# exp30ac.net
KiCad netlist of a schematic drawn in EAGLE
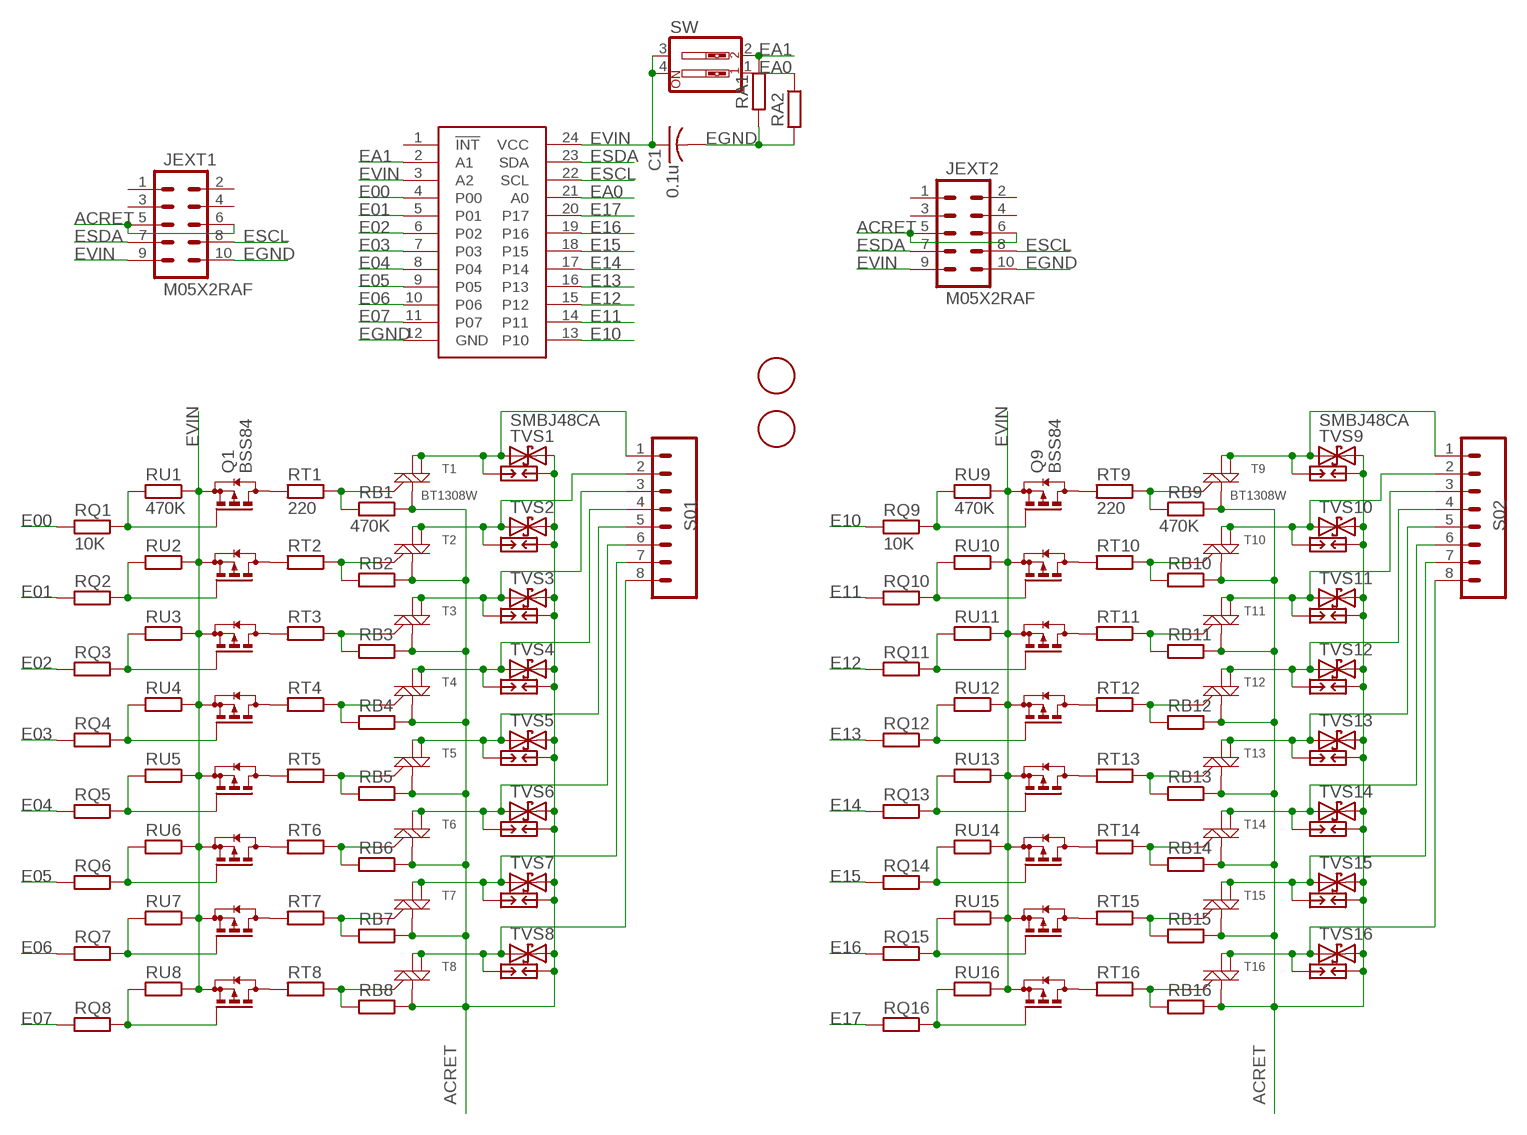
[diagram p0: schematic, sheet 1]

(export (version "E")
  (design (tool "Eeschema 10.0.6"))
  (components
    (comp (ref "C1")
      (value "0.1u")
      (footprint "eagle-import:C0603")
      (libsource (lib "eagle-import") (part "C-USC0603"))
    )
    (comp (ref "JEXT1")
      (value "M05X2RAF")
      (footprint "eagle-import:2X5-RAF")
      (libsource (lib "eagle-import") (part "M05X2RAF"))
    )
    (comp (ref "JEXT2")
      (value "M05X2RAF")
      (footprint "eagle-import:2X5-RAF")
      (libsource (lib "eagle-import") (part "M05X2RAF"))
    )
    (comp (ref "PCF8575")
      (value "PCF8575")
      (footprint "eagle-import:SSOP24")
      (libsource (lib "eagle-import") (part "PCF8575"))
    )
    (comp (ref "Q1")
      (value "BSS84")
      (footprint "eagle-import:SOT23")
      (libsource (lib "eagle-import") (part "BSS84"))
    )
    (comp (ref "Q2")
      (value "BSS84")
      (footprint "eagle-import:SOT23")
      (libsource (lib "eagle-import") (part "BSS84"))
    )
    (comp (ref "Q3")
      (value "BSS84")
      (footprint "eagle-import:SOT23")
      (libsource (lib "eagle-import") (part "BSS84"))
    )
    (comp (ref "Q4")
      (value "BSS84")
      (footprint "eagle-import:SOT23")
      (libsource (lib "eagle-import") (part "BSS84"))
    )
    (comp (ref "Q5")
      (value "BSS84")
      (footprint "eagle-import:SOT23")
      (libsource (lib "eagle-import") (part "BSS84"))
    )
    (comp (ref "Q6")
      (value "BSS84")
      (footprint "eagle-import:SOT23")
      (libsource (lib "eagle-import") (part "BSS84"))
    )
    (comp (ref "Q7")
      (value "BSS84")
      (footprint "eagle-import:SOT23")
      (libsource (lib "eagle-import") (part "BSS84"))
    )
    (comp (ref "Q8")
      (value "BSS84")
      (footprint "eagle-import:SOT23")
      (libsource (lib "eagle-import") (part "BSS84"))
    )
    (comp (ref "Q9")
      (value "BSS84")
      (footprint "eagle-import:SOT23")
      (libsource (lib "eagle-import") (part "BSS84"))
    )
    (comp (ref "Q10")
      (value "BSS84")
      (footprint "eagle-import:SOT23")
      (libsource (lib "eagle-import") (part "BSS84"))
    )
    (comp (ref "Q11")
      (value "BSS84")
      (footprint "eagle-import:SOT23")
      (libsource (lib "eagle-import") (part "BSS84"))
    )
    (comp (ref "Q12")
      (value "BSS84")
      (footprint "eagle-import:SOT23")
      (libsource (lib "eagle-import") (part "BSS84"))
    )
    (comp (ref "Q13")
      (value "BSS84")
      (footprint "eagle-import:SOT23")
      (libsource (lib "eagle-import") (part "BSS84"))
    )
    (comp (ref "Q14")
      (value "BSS84")
      (footprint "eagle-import:SOT23")
      (libsource (lib "eagle-import") (part "BSS84"))
    )
    (comp (ref "Q15")
      (value "BSS84")
      (footprint "eagle-import:SOT23")
      (libsource (lib "eagle-import") (part "BSS84"))
    )
    (comp (ref "Q16")
      (value "BSS84")
      (footprint "eagle-import:SOT23")
      (libsource (lib "eagle-import") (part "BSS84"))
    )
    (comp (ref "RA1")
      (value "10K")
      (footprint "eagle-import:R0603")
      (libsource (lib "eagle-import") (part "R-EU_R0603"))
    )
    (comp (ref "RA2")
      (value "10K")
      (footprint "eagle-import:R0603")
      (libsource (lib "eagle-import") (part "R-EU_R0603"))
    )
    (comp (ref "RB1")
      (value "470K")
      (footprint "eagle-import:R0603")
      (libsource (lib "eagle-import") (part "R-EU_R0603"))
    )
    (comp (ref "RB2")
      (value "470K")
      (footprint "eagle-import:R0603")
      (libsource (lib "eagle-import") (part "R-EU_R0603"))
    )
    (comp (ref "RB3")
      (value "470K")
      (footprint "eagle-import:R0603")
      (libsource (lib "eagle-import") (part "R-EU_R0603"))
    )
    (comp (ref "RB4")
      (value "470K")
      (footprint "eagle-import:R0603")
      (libsource (lib "eagle-import") (part "R-EU_R0603"))
    )
    (comp (ref "RB5")
      (value "470K")
      (footprint "eagle-import:R0603")
      (libsource (lib "eagle-import") (part "R-EU_R0603"))
    )
    (comp (ref "RB6")
      (value "470K")
      (footprint "eagle-import:R0603")
      (libsource (lib "eagle-import") (part "R-EU_R0603"))
    )
    (comp (ref "RB7")
      (value "470K")
      (footprint "eagle-import:R0603")
      (libsource (lib "eagle-import") (part "R-EU_R0603"))
    )
    (comp (ref "RB8")
      (value "470K")
      (footprint "eagle-import:R0603")
      (libsource (lib "eagle-import") (part "R-EU_R0603"))
    )
    (comp (ref "RB9")
      (value "470K")
      (footprint "eagle-import:R0603")
      (libsource (lib "eagle-import") (part "R-EU_R0603"))
    )
    (comp (ref "RB10")
      (value "470K")
      (footprint "eagle-import:R0603")
      (libsource (lib "eagle-import") (part "R-EU_R0603"))
    )
    (comp (ref "RB11")
      (value "470K")
      (footprint "eagle-import:R0603")
      (libsource (lib "eagle-import") (part "R-EU_R0603"))
    )
    (comp (ref "RB12")
      (value "470K")
      (footprint "eagle-import:R0603")
      (libsource (lib "eagle-import") (part "R-EU_R0603"))
    )
    (comp (ref "RB13")
      (value "470K")
      (footprint "eagle-import:R0603")
      (libsource (lib "eagle-import") (part "R-EU_R0603"))
    )
    (comp (ref "RB14")
      (value "470K")
      (footprint "eagle-import:R0603")
      (libsource (lib "eagle-import") (part "R-EU_R0603"))
    )
    (comp (ref "RB15")
      (value "470K")
      (footprint "eagle-import:R0603")
      (libsource (lib "eagle-import") (part "R-EU_R0603"))
    )
    (comp (ref "RB16")
      (value "470K")
      (footprint "eagle-import:R0603")
      (libsource (lib "eagle-import") (part "R-EU_R0603"))
    )
    (comp (ref "RQ1")
      (value "10K")
      (footprint "eagle-import:R0603")
      (libsource (lib "eagle-import") (part "R-EU_R0603"))
    )
    (comp (ref "RQ2")
      (value "10K")
      (footprint "eagle-import:R0603")
      (libsource (lib "eagle-import") (part "R-EU_R0603"))
    )
    (comp (ref "RQ3")
      (value "10K")
      (footprint "eagle-import:R0603")
      (libsource (lib "eagle-import") (part "R-EU_R0603"))
    )
    (comp (ref "RQ4")
      (value "10K")
      (footprint "eagle-import:R0603")
      (libsource (lib "eagle-import") (part "R-EU_R0603"))
    )
    (comp (ref "RQ5")
      (value "10K")
      (footprint "eagle-import:R0603")
      (libsource (lib "eagle-import") (part "R-EU_R0603"))
    )
    (comp (ref "RQ6")
      (value "10K")
      (footprint "eagle-import:R0603")
      (libsource (lib "eagle-import") (part "R-EU_R0603"))
    )
    (comp (ref "RQ7")
      (value "10K")
      (footprint "eagle-import:R0603")
      (libsource (lib "eagle-import") (part "R-EU_R0603"))
    )
    (comp (ref "RQ8")
      (value "10K")
      (footprint "eagle-import:R0603")
      (libsource (lib "eagle-import") (part "R-EU_R0603"))
    )
    (comp (ref "RQ9")
      (value "10K")
      (footprint "eagle-import:R0603")
      (libsource (lib "eagle-import") (part "R-EU_R0603"))
    )
    (comp (ref "RQ10")
      (value "10K")
      (footprint "eagle-import:R0603")
      (libsource (lib "eagle-import") (part "R-EU_R0603"))
    )
    (comp (ref "RQ11")
      (value "10K")
      (footprint "eagle-import:R0603")
      (libsource (lib "eagle-import") (part "R-EU_R0603"))
    )
    (comp (ref "RQ12")
      (value "10K")
      (footprint "eagle-import:R0603")
      (libsource (lib "eagle-import") (part "R-EU_R0603"))
    )
    (comp (ref "RQ13")
      (value "10K")
      (footprint "eagle-import:R0603")
      (libsource (lib "eagle-import") (part "R-EU_R0603"))
    )
    (comp (ref "RQ14")
      (value "10K")
      (footprint "eagle-import:R0603")
      (libsource (lib "eagle-import") (part "R-EU_R0603"))
    )
    (comp (ref "RQ15")
      (value "10K")
      (footprint "eagle-import:R0603")
      (libsource (lib "eagle-import") (part "R-EU_R0603"))
    )
    (comp (ref "RQ16")
      (value "10K")
      (footprint "eagle-import:R0603")
      (libsource (lib "eagle-import") (part "R-EU_R0603"))
    )
    (comp (ref "RT1")
      (value "220")
      (footprint "eagle-import:R0603")
      (libsource (lib "eagle-import") (part "R-EU_R0603"))
    )
    (comp (ref "RT2")
      (value "220")
      (footprint "eagle-import:R0603")
      (libsource (lib "eagle-import") (part "R-EU_R0603"))
    )
    (comp (ref "RT3")
      (value "220")
      (footprint "eagle-import:R0603")
      (libsource (lib "eagle-import") (part "R-EU_R0603"))
    )
    (comp (ref "RT4")
      (value "220")
      (footprint "eagle-import:R0603")
      (libsource (lib "eagle-import") (part "R-EU_R0603"))
    )
    (comp (ref "RT5")
      (value "220")
      (footprint "eagle-import:R0603")
      (libsource (lib "eagle-import") (part "R-EU_R0603"))
    )
    (comp (ref "RT6")
      (value "220")
      (footprint "eagle-import:R0603")
      (libsource (lib "eagle-import") (part "R-EU_R0603"))
    )
    (comp (ref "RT7")
      (value "220")
      (footprint "eagle-import:R0603")
      (libsource (lib "eagle-import") (part "R-EU_R0603"))
    )
    (comp (ref "RT8")
      (value "220")
      (footprint "eagle-import:R0603")
      (libsource (lib "eagle-import") (part "R-EU_R0603"))
    )
    (comp (ref "RT9")
      (value "220")
      (footprint "eagle-import:R0603")
      (libsource (lib "eagle-import") (part "R-EU_R0603"))
    )
    (comp (ref "RT10")
      (value "220")
      (footprint "eagle-import:R0603")
      (libsource (lib "eagle-import") (part "R-EU_R0603"))
    )
    (comp (ref "RT11")
      (value "220")
      (footprint "eagle-import:R0603")
      (libsource (lib "eagle-import") (part "R-EU_R0603"))
    )
    (comp (ref "RT12")
      (value "220")
      (footprint "eagle-import:R0603")
      (libsource (lib "eagle-import") (part "R-EU_R0603"))
    )
    (comp (ref "RT13")
      (value "220")
      (footprint "eagle-import:R0603")
      (libsource (lib "eagle-import") (part "R-EU_R0603"))
    )
    (comp (ref "RT14")
      (value "220")
      (footprint "eagle-import:R0603")
      (libsource (lib "eagle-import") (part "R-EU_R0603"))
    )
    (comp (ref "RT15")
      (value "220")
      (footprint "eagle-import:R0603")
      (libsource (lib "eagle-import") (part "R-EU_R0603"))
    )
    (comp (ref "RT16")
      (value "220")
      (footprint "eagle-import:R0603")
      (libsource (lib "eagle-import") (part "R-EU_R0603"))
    )
    (comp (ref "RU1")
      (value "470K")
      (footprint "eagle-import:R0603")
      (libsource (lib "eagle-import") (part "R-EU_R0603"))
    )
    (comp (ref "RU2")
      (value "470K")
      (footprint "eagle-import:R0603")
      (libsource (lib "eagle-import") (part "R-EU_R0603"))
    )
    (comp (ref "RU3")
      (value "470K")
      (footprint "eagle-import:R0603")
      (libsource (lib "eagle-import") (part "R-EU_R0603"))
    )
    (comp (ref "RU4")
      (value "470K")
      (footprint "eagle-import:R0603")
      (libsource (lib "eagle-import") (part "R-EU_R0603"))
    )
    (comp (ref "RU5")
      (value "470K")
      (footprint "eagle-import:R0603")
      (libsource (lib "eagle-import") (part "R-EU_R0603"))
    )
    (comp (ref "RU6")
      (value "470K")
      (footprint "eagle-import:R0603")
      (libsource (lib "eagle-import") (part "R-EU_R0603"))
    )
    (comp (ref "RU7")
      (value "470K")
      (footprint "eagle-import:R0603")
      (libsource (lib "eagle-import") (part "R-EU_R0603"))
    )
    (comp (ref "RU8")
      (value "470K")
      (footprint "eagle-import:R0603")
      (libsource (lib "eagle-import") (part "R-EU_R0603"))
    )
    (comp (ref "RU9")
      (value "470K")
      (footprint "eagle-import:R0603")
      (libsource (lib "eagle-import") (part "R-EU_R0603"))
    )
    (comp (ref "RU10")
      (value "470K")
      (footprint "eagle-import:R0603")
      (libsource (lib "eagle-import") (part "R-EU_R0603"))
    )
    (comp (ref "RU11")
      (value "470K")
      (footprint "eagle-import:R0603")
      (libsource (lib "eagle-import") (part "R-EU_R0603"))
    )
    (comp (ref "RU12")
      (value "470K")
      (footprint "eagle-import:R0603")
      (libsource (lib "eagle-import") (part "R-EU_R0603"))
    )
    (comp (ref "RU13")
      (value "470K")
      (footprint "eagle-import:R0603")
      (libsource (lib "eagle-import") (part "R-EU_R0603"))
    )
    (comp (ref "RU14")
      (value "470K")
      (footprint "eagle-import:R0603")
      (libsource (lib "eagle-import") (part "R-EU_R0603"))
    )
    (comp (ref "RU15")
      (value "470K")
      (footprint "eagle-import:R0603")
      (libsource (lib "eagle-import") (part "R-EU_R0603"))
    )
    (comp (ref "RU16")
      (value "470K")
      (footprint "eagle-import:R0603")
      (libsource (lib "eagle-import") (part "R-EU_R0603"))
    )
    (comp (ref "S01")
      (value "M085MM-8")
      (footprint "eagle-import:SCREWTERMINAL-5MM-8")
      (libsource (lib "eagle-import") (part "M085MM-8"))
    )
    (comp (ref "S02")
      (value "M085MM-8")
      (footprint "eagle-import:SCREWTERMINAL-5MM-8")
      (libsource (lib "eagle-import") (part "M085MM-8"))
    )
    (comp (ref "SP1")
      (value "PCB-SGAP")
      (footprint "eagle-import:PCB-SGAP")
      (libsource (lib "eagle-import") (part "PCB-SGAP"))
    )
    (comp (ref "SP2")
      (value "PCB-SGAP")
      (footprint "eagle-import:PCB-SGAP")
      (libsource (lib "eagle-import") (part "PCB-SGAP"))
    )
    (comp (ref "SP3")
      (value "PCB-SGAP")
      (footprint "eagle-import:PCB-SGAP")
      (libsource (lib "eagle-import") (part "PCB-SGAP"))
    )
    (comp (ref "SP4")
      (value "PCB-SGAP")
      (footprint "eagle-import:PCB-SGAP")
      (libsource (lib "eagle-import") (part "PCB-SGAP"))
    )
    (comp (ref "SP5")
      (value "PCB-SGAP")
      (footprint "eagle-import:PCB-SGAP")
      (libsource (lib "eagle-import") (part "PCB-SGAP"))
    )
    (comp (ref "SP6")
      (value "PCB-SGAP")
      (footprint "eagle-import:PCB-SGAP")
      (libsource (lib "eagle-import") (part "PCB-SGAP"))
    )
    (comp (ref "SP7")
      (value "PCB-SGAP")
      (footprint "eagle-import:PCB-SGAP")
      (libsource (lib "eagle-import") (part "PCB-SGAP"))
    )
    (comp (ref "SP8")
      (value "PCB-SGAP")
      (footprint "eagle-import:PCB-SGAP")
      (libsource (lib "eagle-import") (part "PCB-SGAP"))
    )
    (comp (ref "SP9")
      (value "PCB-SGAP")
      (footprint "eagle-import:PCB-SGAP")
      (libsource (lib "eagle-import") (part "PCB-SGAP"))
    )
    (comp (ref "SP10")
      (value "PCB-SGAP")
      (footprint "eagle-import:PCB-SGAP")
      (libsource (lib "eagle-import") (part "PCB-SGAP"))
    )
    (comp (ref "SP11")
      (value "PCB-SGAP")
      (footprint "eagle-import:PCB-SGAP")
      (libsource (lib "eagle-import") (part "PCB-SGAP"))
    )
    (comp (ref "SP12")
      (value "PCB-SGAP")
      (footprint "eagle-import:PCB-SGAP")
      (libsource (lib "eagle-import") (part "PCB-SGAP"))
    )
    (comp (ref "SP13")
      (value "PCB-SGAP")
      (footprint "eagle-import:PCB-SGAP")
      (libsource (lib "eagle-import") (part "PCB-SGAP"))
    )
    (comp (ref "SP14")
      (value "PCB-SGAP")
      (footprint "eagle-import:PCB-SGAP")
      (libsource (lib "eagle-import") (part "PCB-SGAP"))
    )
    (comp (ref "SP15")
      (value "PCB-SGAP")
      (footprint "eagle-import:PCB-SGAP")
      (libsource (lib "eagle-import") (part "PCB-SGAP"))
    )
    (comp (ref "SP16")
      (value "PCB-SGAP")
      (footprint "eagle-import:PCB-SGAP")
      (libsource (lib "eagle-import") (part "PCB-SGAP"))
    )
    (comp (ref "SW")
      (value "SW_DIP-2")
      (footprint "eagle-import:DIPSWITCH-02")
      (libsource (lib "eagle-import") (part "SW_DIP-2"))
    )
    (comp (ref "T1")
      (value "BT1308W")
      (footprint "eagle-import:SOT223")
      (libsource (lib "eagle-import") (part "MAC97SOT223"))
    )
    (comp (ref "T2")
      (value "MAC97SOT223")
      (footprint "eagle-import:SOT223")
      (libsource (lib "eagle-import") (part "MAC97SOT223"))
    )
    (comp (ref "T3")
      (value "MAC97SOT223")
      (footprint "eagle-import:SOT223")
      (libsource (lib "eagle-import") (part "MAC97SOT223"))
    )
    (comp (ref "T4")
      (value "MAC97SOT223")
      (footprint "eagle-import:SOT223")
      (libsource (lib "eagle-import") (part "MAC97SOT223"))
    )
    (comp (ref "T5")
      (value "MAC97SOT223")
      (footprint "eagle-import:SOT223")
      (libsource (lib "eagle-import") (part "MAC97SOT223"))
    )
    (comp (ref "T6")
      (value "MAC97SOT223")
      (footprint "eagle-import:SOT223")
      (libsource (lib "eagle-import") (part "MAC97SOT223"))
    )
    (comp (ref "T7")
      (value "MAC97SOT223")
      (footprint "eagle-import:SOT223")
      (libsource (lib "eagle-import") (part "MAC97SOT223"))
    )
    (comp (ref "T8")
      (value "MAC97SOT223")
      (footprint "eagle-import:SOT223")
      (libsource (lib "eagle-import") (part "MAC97SOT223"))
    )
    (comp (ref "T9")
      (value "BT1308W")
      (footprint "eagle-import:SOT223")
      (libsource (lib "eagle-import") (part "MAC97SOT223"))
    )
    (comp (ref "T10")
      (value "MAC97SOT223")
      (footprint "eagle-import:SOT223")
      (libsource (lib "eagle-import") (part "MAC97SOT223"))
    )
    (comp (ref "T11")
      (value "MAC97SOT223")
      (footprint "eagle-import:SOT223")
      (libsource (lib "eagle-import") (part "MAC97SOT223"))
    )
    (comp (ref "T12")
      (value "MAC97SOT223")
      (footprint "eagle-import:SOT223")
      (libsource (lib "eagle-import") (part "MAC97SOT223"))
    )
    (comp (ref "T13")
      (value "MAC97SOT223")
      (footprint "eagle-import:SOT223")
      (libsource (lib "eagle-import") (part "MAC97SOT223"))
    )
    (comp (ref "T14")
      (value "MAC97SOT223")
      (footprint "eagle-import:SOT223")
      (libsource (lib "eagle-import") (part "MAC97SOT223"))
    )
    (comp (ref "T15")
      (value "MAC97SOT223")
      (footprint "eagle-import:SOT223")
      (libsource (lib "eagle-import") (part "MAC97SOT223"))
    )
    (comp (ref "T16")
      (value "MAC97SOT223")
      (footprint "eagle-import:SOT223")
      (libsource (lib "eagle-import") (part "MAC97SOT223"))
    )
    (comp (ref "TVS1")
      (value "SMBJ48CA")
      (footprint "eagle-import:SMB")
      (libsource (lib "eagle-import") (part "TVSSMB"))
    )
    (comp (ref "TVS2")
      (value "TVSSMB")
      (footprint "eagle-import:SMB")
      (libsource (lib "eagle-import") (part "TVSSMB"))
    )
    (comp (ref "TVS3")
      (value "TVSSMB")
      (footprint "eagle-import:SMB")
      (libsource (lib "eagle-import") (part "TVSSMB"))
    )
    (comp (ref "TVS4")
      (value "TVSSMB")
      (footprint "eagle-import:SMB")
      (libsource (lib "eagle-import") (part "TVSSMB"))
    )
    (comp (ref "TVS5")
      (value "TVSSMB")
      (footprint "eagle-import:SMB")
      (libsource (lib "eagle-import") (part "TVSSMB"))
    )
    (comp (ref "TVS6")
      (value "TVSSMB")
      (footprint "eagle-import:SMB")
      (libsource (lib "eagle-import") (part "TVSSMB"))
    )
    (comp (ref "TVS7")
      (value "TVSSMB")
      (footprint "eagle-import:SMB")
      (libsource (lib "eagle-import") (part "TVSSMB"))
    )
    (comp (ref "TVS8")
      (value "TVSSMB")
      (footprint "eagle-import:SMB")
      (libsource (lib "eagle-import") (part "TVSSMB"))
    )
    (comp (ref "TVS9")
      (value "SMBJ48CA")
      (footprint "eagle-import:SMB")
      (libsource (lib "eagle-import") (part "TVSSMB"))
    )
    (comp (ref "TVS10")
      (value "TVSSMB")
      (footprint "eagle-import:SMB")
      (libsource (lib "eagle-import") (part "TVSSMB"))
    )
    (comp (ref "TVS11")
      (value "TVSSMB")
      (footprint "eagle-import:SMB")
      (libsource (lib "eagle-import") (part "TVSSMB"))
    )
    (comp (ref "TVS12")
      (value "TVSSMB")
      (footprint "eagle-import:SMB")
      (libsource (lib "eagle-import") (part "TVSSMB"))
    )
    (comp (ref "TVS13")
      (value "TVSSMB")
      (footprint "eagle-import:SMB")
      (libsource (lib "eagle-import") (part "TVSSMB"))
    )
    (comp (ref "TVS14")
      (value "TVSSMB")
      (footprint "eagle-import:SMB")
      (libsource (lib "eagle-import") (part "TVSSMB"))
    )
    (comp (ref "TVS15")
      (value "TVSSMB")
      (footprint "eagle-import:SMB")
      (libsource (lib "eagle-import") (part "TVSSMB"))
    )
    (comp (ref "TVS16")
      (value "TVSSMB")
      (footprint "eagle-import:SMB")
      (libsource (lib "eagle-import") (part "TVSSMB"))
    )
    (comp (ref "U$1")
      (value "FIDUCIAL")
      (footprint "eagle-import:FIDUCIAL_1MM")
      (libsource (lib "eagle-import") (part "FIDUCIAL"))
    )
    (comp (ref "U$2")
      (value "FIDUCIAL")
      (footprint "eagle-import:FIDUCIAL_1MM")
      (libsource (lib "eagle-import") (part "FIDUCIAL"))
    )
  )
  (nets
    (net (code "1") (name "/ACRET") (class "Default")
      (node (ref "JEXT1") (pin "5") (pinfunction "5_5") (pintype "passive"))
      (node (ref "JEXT1") (pin "6") (pinfunction "6_6") (pintype "passive"))
      (node (ref "JEXT2") (pin "5") (pinfunction "5_5") (pintype "passive"))
      (node (ref "JEXT2") (pin "6") (pinfunction "6_6") (pintype "passive"))
      (node (ref "RB1") (pin "1") (pinfunction "1_1") (pintype "passive"))
      (node (ref "RB10") (pin "1") (pinfunction "1_1") (pintype "passive"))
      (node (ref "RB11") (pin "1") (pinfunction "1_1") (pintype "passive"))
      (node (ref "RB12") (pin "1") (pinfunction "1_1") (pintype "passive"))
      (node (ref "RB13") (pin "1") (pinfunction "1_1") (pintype "passive"))
      (node (ref "RB14") (pin "1") (pinfunction "1_1") (pintype "passive"))
      (node (ref "RB15") (pin "1") (pinfunction "1_1") (pintype "passive"))
      (node (ref "RB16") (pin "1") (pinfunction "1_1") (pintype "passive"))
      (node (ref "RB2") (pin "1") (pinfunction "1_1") (pintype "passive"))
      (node (ref "RB3") (pin "1") (pinfunction "1_1") (pintype "passive"))
      (node (ref "RB4") (pin "1") (pinfunction "1_1") (pintype "passive"))
      (node (ref "RB5") (pin "1") (pinfunction "1_1") (pintype "passive"))
      (node (ref "RB6") (pin "1") (pinfunction "1_1") (pintype "passive"))
      (node (ref "RB7") (pin "1") (pinfunction "1_1") (pintype "passive"))
      (node (ref "RB8") (pin "1") (pinfunction "1_1") (pintype "passive"))
      (node (ref "RB9") (pin "1") (pinfunction "1_1") (pintype "passive"))
      (node (ref "SP1") (pin "1") (pinfunction "1_1") (pintype "passive"))
      (node (ref "SP10") (pin "1") (pinfunction "1_1") (pintype "passive"))
      (node (ref "SP11") (pin "1") (pinfunction "1_1") (pintype "passive"))
      (node (ref "SP12") (pin "1") (pinfunction "1_1") (pintype "passive"))
      (node (ref "SP13") (pin "1") (pinfunction "1_1") (pintype "passive"))
      (node (ref "SP14") (pin "1") (pinfunction "1_1") (pintype "passive"))
      (node (ref "SP15") (pin "1") (pinfunction "1_1") (pintype "passive"))
      (node (ref "SP16") (pin "1") (pinfunction "1_1") (pintype "passive"))
      (node (ref "SP2") (pin "1") (pinfunction "1_1") (pintype "passive"))
      (node (ref "SP3") (pin "1") (pinfunction "1_1") (pintype "passive"))
      (node (ref "SP4") (pin "1") (pinfunction "1_1") (pintype "passive"))
      (node (ref "SP5") (pin "1") (pinfunction "1_1") (pintype "passive"))
      (node (ref "SP6") (pin "1") (pinfunction "1_1") (pintype "passive"))
      (node (ref "SP7") (pin "1") (pinfunction "1_1") (pintype "passive"))
      (node (ref "SP8") (pin "1") (pinfunction "1_1") (pintype "passive"))
      (node (ref "SP9") (pin "1") (pinfunction "1_1") (pintype "passive"))
      (node (ref "T1") (pin "1") (pinfunction "M1_1") (pintype "bidirectional"))
      (node (ref "T10") (pin "1") (pinfunction "M1_1") (pintype "bidirectional"))
      (node (ref "T11") (pin "1") (pinfunction "M1_1") (pintype "bidirectional"))
      (node (ref "T12") (pin "1") (pinfunction "M1_1") (pintype "bidirectional"))
      (node (ref "T13") (pin "1") (pinfunction "M1_1") (pintype "bidirectional"))
      (node (ref "T14") (pin "1") (pinfunction "M1_1") (pintype "bidirectional"))
      (node (ref "T15") (pin "1") (pinfunction "M1_1") (pintype "bidirectional"))
      (node (ref "T16") (pin "1") (pinfunction "M1_1") (pintype "bidirectional"))
      (node (ref "T2") (pin "1") (pinfunction "M1_1") (pintype "bidirectional"))
      (node (ref "T3") (pin "1") (pinfunction "M1_1") (pintype "bidirectional"))
      (node (ref "T4") (pin "1") (pinfunction "M1_1") (pintype "bidirectional"))
      (node (ref "T5") (pin "1") (pinfunction "M1_1") (pintype "bidirectional"))
      (node (ref "T6") (pin "1") (pinfunction "M1_1") (pintype "bidirectional"))
      (node (ref "T7") (pin "1") (pinfunction "M1_1") (pintype "bidirectional"))
      (node (ref "T8") (pin "1") (pinfunction "M1_1") (pintype "bidirectional"))
      (node (ref "T9") (pin "1") (pinfunction "M1_1") (pintype "bidirectional"))
      (node (ref "TVS1") (pin "C") (pinfunction "C_C") (pintype "passive"))
      (node (ref "TVS10") (pin "C") (pinfunction "C_C") (pintype "passive"))
      (node (ref "TVS11") (pin "C") (pinfunction "C_C") (pintype "passive"))
      (node (ref "TVS12") (pin "C") (pinfunction "C_C") (pintype "passive"))
      (node (ref "TVS13") (pin "C") (pinfunction "C_C") (pintype "passive"))
      (node (ref "TVS14") (pin "C") (pinfunction "C_C") (pintype "passive"))
      (node (ref "TVS15") (pin "C") (pinfunction "C_C") (pintype "passive"))
      (node (ref "TVS16") (pin "C") (pinfunction "C_C") (pintype "passive"))
      (node (ref "TVS2") (pin "C") (pinfunction "C_C") (pintype "passive"))
      (node (ref "TVS3") (pin "C") (pinfunction "C_C") (pintype "passive"))
      (node (ref "TVS4") (pin "C") (pinfunction "C_C") (pintype "passive"))
      (node (ref "TVS5") (pin "C") (pinfunction "C_C") (pintype "passive"))
      (node (ref "TVS6") (pin "C") (pinfunction "C_C") (pintype "passive"))
      (node (ref "TVS7") (pin "C") (pinfunction "C_C") (pintype "passive"))
      (node (ref "TVS8") (pin "C") (pinfunction "C_C") (pintype "passive"))
      (node (ref "TVS9") (pin "C") (pinfunction "C_C") (pintype "passive"))
    )
    (net (code "2") (name "/E00") (class "Default")
      (node (ref "PCF8575") (pin "4") (pinfunction "P00_4") (pintype "bidirectional"))
      (node (ref "RQ1") (pin "2") (pinfunction "2_2") (pintype "passive"))
    )
    (net (code "3") (name "/E01") (class "Default")
      (node (ref "PCF8575") (pin "5") (pinfunction "P01_5") (pintype "bidirectional"))
      (node (ref "RQ2") (pin "2") (pinfunction "2_2") (pintype "passive"))
    )
    (net (code "4") (name "/E02") (class "Default")
      (node (ref "PCF8575") (pin "6") (pinfunction "P02_6") (pintype "bidirectional"))
      (node (ref "RQ3") (pin "2") (pinfunction "2_2") (pintype "passive"))
    )
    (net (code "5") (name "/E03") (class "Default")
      (node (ref "PCF8575") (pin "7") (pinfunction "P03_7") (pintype "bidirectional"))
      (node (ref "RQ4") (pin "2") (pinfunction "2_2") (pintype "passive"))
    )
    (net (code "6") (name "/E04") (class "Default")
      (node (ref "PCF8575") (pin "8") (pinfunction "P04_8") (pintype "bidirectional"))
      (node (ref "RQ5") (pin "2") (pinfunction "2_2") (pintype "passive"))
    )
    (net (code "7") (name "/E05") (class "Default")
      (node (ref "PCF8575") (pin "9") (pinfunction "P05_9") (pintype "bidirectional"))
      (node (ref "RQ6") (pin "2") (pinfunction "2_2") (pintype "passive"))
    )
    (net (code "8") (name "/E06") (class "Default")
      (node (ref "PCF8575") (pin "10") (pinfunction "P06_10") (pintype "bidirectional"))
      (node (ref "RQ7") (pin "2") (pinfunction "2_2") (pintype "passive"))
    )
    (net (code "9") (name "/E07") (class "Default")
      (node (ref "PCF8575") (pin "11") (pinfunction "P07_11") (pintype "bidirectional"))
      (node (ref "RQ8") (pin "2") (pinfunction "2_2") (pintype "passive"))
    )
    (net (code "10") (name "/E10") (class "Default")
      (node (ref "PCF8575") (pin "13") (pinfunction "P10_13") (pintype "bidirectional"))
      (node (ref "RQ9") (pin "2") (pinfunction "2_2") (pintype "passive"))
    )
    (net (code "11") (name "/E11") (class "Default")
      (node (ref "PCF8575") (pin "14") (pinfunction "P11_14") (pintype "bidirectional"))
      (node (ref "RQ10") (pin "2") (pinfunction "2_2") (pintype "passive"))
    )
    (net (code "12") (name "/E12") (class "Default")
      (node (ref "PCF8575") (pin "15") (pinfunction "P12_15") (pintype "bidirectional"))
      (node (ref "RQ11") (pin "2") (pinfunction "2_2") (pintype "passive"))
    )
    (net (code "13") (name "/E13") (class "Default")
      (node (ref "PCF8575") (pin "16") (pinfunction "P13_16") (pintype "bidirectional"))
      (node (ref "RQ12") (pin "2") (pinfunction "2_2") (pintype "passive"))
    )
    (net (code "14") (name "/E14") (class "Default")
      (node (ref "PCF8575") (pin "17") (pinfunction "P14_17") (pintype "bidirectional"))
      (node (ref "RQ13") (pin "2") (pinfunction "2_2") (pintype "passive"))
    )
    (net (code "15") (name "/E15") (class "Default")
      (node (ref "PCF8575") (pin "18") (pinfunction "P15_18") (pintype "bidirectional"))
      (node (ref "RQ14") (pin "2") (pinfunction "2_2") (pintype "passive"))
    )
    (net (code "16") (name "/E16") (class "Default")
      (node (ref "PCF8575") (pin "19") (pinfunction "P16_19") (pintype "bidirectional"))
      (node (ref "RQ15") (pin "2") (pinfunction "2_2") (pintype "passive"))
    )
    (net (code "17") (name "/E17") (class "Default")
      (node (ref "PCF8575") (pin "20") (pinfunction "P17_20") (pintype "bidirectional"))
      (node (ref "RQ16") (pin "2") (pinfunction "2_2") (pintype "passive"))
    )
    (net (code "18") (name "/EA0") (class "Default")
      (node (ref "PCF8575") (pin "21") (pinfunction "A0_21") (pintype "bidirectional"))
      (node (ref "RA2") (pin "1") (pinfunction "1_1") (pintype "passive"))
      (node (ref "SW") (pin "1") (pinfunction "1_1") (pintype "passive"))
    )
    (net (code "19") (name "/EA1") (class "Default")
      (node (ref "PCF8575") (pin "2") (pinfunction "A1_2") (pintype "bidirectional"))
      (node (ref "RA1") (pin "1") (pinfunction "1_1") (pintype "passive"))
      (node (ref "SW") (pin "2") (pinfunction "2_2") (pintype "passive"))
    )
    (net (code "20") (name "/EGND") (class "Default")
      (node (ref "C1") (pin "2") (pinfunction "2_2") (pintype "passive"))
      (node (ref "JEXT1") (pin "10") (pinfunction "10_10") (pintype "passive"))
      (node (ref "JEXT2") (pin "10") (pinfunction "10_10") (pintype "passive"))
      (node (ref "PCF8575") (pin "12") (pinfunction "GND_12") (pintype "power_in"))
      (node (ref "RA1") (pin "2") (pinfunction "2_2") (pintype "passive"))
      (node (ref "RA2") (pin "2") (pinfunction "2_2") (pintype "passive"))
    )
    (net (code "21") (name "/ESCL") (class "Default")
      (node (ref "JEXT1") (pin "8") (pinfunction "8_8") (pintype "passive"))
      (node (ref "JEXT2") (pin "8") (pinfunction "8_8") (pintype "passive"))
      (node (ref "PCF8575") (pin "22") (pinfunction "SCL_22") (pintype "bidirectional"))
    )
    (net (code "22") (name "/ESDA") (class "Default")
      (node (ref "JEXT1") (pin "7") (pinfunction "7_7") (pintype "passive"))
      (node (ref "JEXT2") (pin "7") (pinfunction "7_7") (pintype "passive"))
      (node (ref "PCF8575") (pin "23") (pinfunction "SDA_23") (pintype "bidirectional"))
    )
    (net (code "23") (name "/EVIN") (class "Default")
      (node (ref "C1") (pin "1") (pinfunction "1_1") (pintype "passive"))
      (node (ref "JEXT1") (pin "9") (pinfunction "9_9") (pintype "passive"))
      (node (ref "JEXT2") (pin "9") (pinfunction "9_9") (pintype "passive"))
      (node (ref "PCF8575") (pin "24") (pinfunction "VCC_24") (pintype "power_in"))
      (node (ref "PCF8575") (pin "3") (pinfunction "A2_3") (pintype "bidirectional"))
      (node (ref "Q1") (pin "2") (pinfunction "S_2") (pintype "passive"))
      (node (ref "Q10") (pin "2") (pinfunction "S_2") (pintype "passive"))
      (node (ref "Q11") (pin "2") (pinfunction "S_2") (pintype "passive"))
      (node (ref "Q12") (pin "2") (pinfunction "S_2") (pintype "passive"))
      (node (ref "Q13") (pin "2") (pinfunction "S_2") (pintype "passive"))
      (node (ref "Q14") (pin "2") (pinfunction "S_2") (pintype "passive"))
      (node (ref "Q15") (pin "2") (pinfunction "S_2") (pintype "passive"))
      (node (ref "Q16") (pin "2") (pinfunction "S_2") (pintype "passive"))
      (node (ref "Q2") (pin "2") (pinfunction "S_2") (pintype "passive"))
      (node (ref "Q3") (pin "2") (pinfunction "S_2") (pintype "passive"))
      (node (ref "Q4") (pin "2") (pinfunction "S_2") (pintype "passive"))
      (node (ref "Q5") (pin "2") (pinfunction "S_2") (pintype "passive"))
      (node (ref "Q6") (pin "2") (pinfunction "S_2") (pintype "passive"))
      (node (ref "Q7") (pin "2") (pinfunction "S_2") (pintype "passive"))
      (node (ref "Q8") (pin "2") (pinfunction "S_2") (pintype "passive"))
      (node (ref "Q9") (pin "2") (pinfunction "S_2") (pintype "passive"))
      (node (ref "RU1") (pin "1") (pinfunction "1_1") (pintype "passive"))
      (node (ref "RU10") (pin "1") (pinfunction "1_1") (pintype "passive"))
      (node (ref "RU11") (pin "1") (pinfunction "1_1") (pintype "passive"))
      (node (ref "RU12") (pin "1") (pinfunction "1_1") (pintype "passive"))
      (node (ref "RU13") (pin "1") (pinfunction "1_1") (pintype "passive"))
      (node (ref "RU14") (pin "1") (pinfunction "1_1") (pintype "passive"))
      (node (ref "RU15") (pin "1") (pinfunction "1_1") (pintype "passive"))
      (node (ref "RU16") (pin "1") (pinfunction "1_1") (pintype "passive"))
      (node (ref "RU2") (pin "1") (pinfunction "1_1") (pintype "passive"))
      (node (ref "RU3") (pin "1") (pinfunction "1_1") (pintype "passive"))
      (node (ref "RU4") (pin "1") (pinfunction "1_1") (pintype "passive"))
      (node (ref "RU5") (pin "1") (pinfunction "1_1") (pintype "passive"))
      (node (ref "RU6") (pin "1") (pinfunction "1_1") (pintype "passive"))
      (node (ref "RU7") (pin "1") (pinfunction "1_1") (pintype "passive"))
      (node (ref "RU8") (pin "1") (pinfunction "1_1") (pintype "passive"))
      (node (ref "RU9") (pin "1") (pinfunction "1_1") (pintype "passive"))
      (node (ref "SW") (pin "3") (pinfunction "3_3") (pintype "passive"))
      (node (ref "SW") (pin "4") (pinfunction "4_4") (pintype "passive"))
    )
    (net (code "24") (name "Net-(Q1-D)") (class "Default")
      (node (ref "Q1") (pin "3") (pinfunction "D_3") (pintype "passive"))
      (node (ref "RT1") (pin "2") (pinfunction "2_2") (pintype "passive"))
    )
    (net (code "25") (name "Net-(Q1-G)") (class "Default")
      (node (ref "Q1") (pin "1") (pinfunction "G_1") (pintype "passive"))
      (node (ref "RQ1") (pin "1") (pinfunction "1_1") (pintype "passive"))
      (node (ref "RU1") (pin "2") (pinfunction "2_2") (pintype "passive"))
    )
    (net (code "26") (name "Net-(Q2-D)") (class "Default")
      (node (ref "Q2") (pin "3") (pinfunction "D_3") (pintype "passive"))
      (node (ref "RT2") (pin "2") (pinfunction "2_2") (pintype "passive"))
    )
    (net (code "27") (name "Net-(Q2-G)") (class "Default")
      (node (ref "Q2") (pin "1") (pinfunction "G_1") (pintype "passive"))
      (node (ref "RQ2") (pin "1") (pinfunction "1_1") (pintype "passive"))
      (node (ref "RU2") (pin "2") (pinfunction "2_2") (pintype "passive"))
    )
    (net (code "28") (name "Net-(Q3-D)") (class "Default")
      (node (ref "Q3") (pin "3") (pinfunction "D_3") (pintype "passive"))
      (node (ref "RT3") (pin "2") (pinfunction "2_2") (pintype "passive"))
    )
    (net (code "29") (name "Net-(Q3-G)") (class "Default")
      (node (ref "Q3") (pin "1") (pinfunction "G_1") (pintype "passive"))
      (node (ref "RQ3") (pin "1") (pinfunction "1_1") (pintype "passive"))
      (node (ref "RU3") (pin "2") (pinfunction "2_2") (pintype "passive"))
    )
    (net (code "30") (name "Net-(Q4-D)") (class "Default")
      (node (ref "Q4") (pin "3") (pinfunction "D_3") (pintype "passive"))
      (node (ref "RT4") (pin "2") (pinfunction "2_2") (pintype "passive"))
    )
    (net (code "31") (name "Net-(Q4-G)") (class "Default")
      (node (ref "Q4") (pin "1") (pinfunction "G_1") (pintype "passive"))
      (node (ref "RQ4") (pin "1") (pinfunction "1_1") (pintype "passive"))
      (node (ref "RU4") (pin "2") (pinfunction "2_2") (pintype "passive"))
    )
    (net (code "32") (name "Net-(Q5-D)") (class "Default")
      (node (ref "Q5") (pin "3") (pinfunction "D_3") (pintype "passive"))
      (node (ref "RT5") (pin "2") (pinfunction "2_2") (pintype "passive"))
    )
    (net (code "33") (name "Net-(Q5-G)") (class "Default")
      (node (ref "Q5") (pin "1") (pinfunction "G_1") (pintype "passive"))
      (node (ref "RQ5") (pin "1") (pinfunction "1_1") (pintype "passive"))
      (node (ref "RU5") (pin "2") (pinfunction "2_2") (pintype "passive"))
    )
    (net (code "34") (name "Net-(Q6-D)") (class "Default")
      (node (ref "Q6") (pin "3") (pinfunction "D_3") (pintype "passive"))
      (node (ref "RT6") (pin "2") (pinfunction "2_2") (pintype "passive"))
    )
    (net (code "35") (name "Net-(Q6-G)") (class "Default")
      (node (ref "Q6") (pin "1") (pinfunction "G_1") (pintype "passive"))
      (node (ref "RQ6") (pin "1") (pinfunction "1_1") (pintype "passive"))
      (node (ref "RU6") (pin "2") (pinfunction "2_2") (pintype "passive"))
    )
    (net (code "36") (name "Net-(Q7-D)") (class "Default")
      (node (ref "Q7") (pin "3") (pinfunction "D_3") (pintype "passive"))
      (node (ref "RT7") (pin "2") (pinfunction "2_2") (pintype "passive"))
    )
    (net (code "37") (name "Net-(Q7-G)") (class "Default")
      (node (ref "Q7") (pin "1") (pinfunction "G_1") (pintype "passive"))
      (node (ref "RQ7") (pin "1") (pinfunction "1_1") (pintype "passive"))
      (node (ref "RU7") (pin "2") (pinfunction "2_2") (pintype "passive"))
    )
    (net (code "38") (name "Net-(Q8-D)") (class "Default")
      (node (ref "Q8") (pin "3") (pinfunction "D_3") (pintype "passive"))
      (node (ref "RT8") (pin "2") (pinfunction "2_2") (pintype "passive"))
    )
    (net (code "39") (name "Net-(Q8-G)") (class "Default")
      (node (ref "Q8") (pin "1") (pinfunction "G_1") (pintype "passive"))
      (node (ref "RQ8") (pin "1") (pinfunction "1_1") (pintype "passive"))
      (node (ref "RU8") (pin "2") (pinfunction "2_2") (pintype "passive"))
    )
    (net (code "40") (name "Net-(Q9-D)") (class "Default")
      (node (ref "Q9") (pin "3") (pinfunction "D_3") (pintype "passive"))
      (node (ref "RT9") (pin "2") (pinfunction "2_2") (pintype "passive"))
    )
    (net (code "41") (name "Net-(Q9-G)") (class "Default")
      (node (ref "Q9") (pin "1") (pinfunction "G_1") (pintype "passive"))
      (node (ref "RQ9") (pin "1") (pinfunction "1_1") (pintype "passive"))
      (node (ref "RU9") (pin "2") (pinfunction "2_2") (pintype "passive"))
    )
    (net (code "42") (name "Net-(Q10-D)") (class "Default")
      (node (ref "Q10") (pin "3") (pinfunction "D_3") (pintype "passive"))
      (node (ref "RT10") (pin "2") (pinfunction "2_2") (pintype "passive"))
    )
    (net (code "43") (name "Net-(Q10-G)") (class "Default")
      (node (ref "Q10") (pin "1") (pinfunction "G_1") (pintype "passive"))
      (node (ref "RQ10") (pin "1") (pinfunction "1_1") (pintype "passive"))
      (node (ref "RU10") (pin "2") (pinfunction "2_2") (pintype "passive"))
    )
    (net (code "44") (name "Net-(Q11-D)") (class "Default")
      (node (ref "Q11") (pin "3") (pinfunction "D_3") (pintype "passive"))
      (node (ref "RT11") (pin "2") (pinfunction "2_2") (pintype "passive"))
    )
    (net (code "45") (name "Net-(Q11-G)") (class "Default")
      (node (ref "Q11") (pin "1") (pinfunction "G_1") (pintype "passive"))
      (node (ref "RQ11") (pin "1") (pinfunction "1_1") (pintype "passive"))
      (node (ref "RU11") (pin "2") (pinfunction "2_2") (pintype "passive"))
    )
    (net (code "46") (name "Net-(Q12-D)") (class "Default")
      (node (ref "Q12") (pin "3") (pinfunction "D_3") (pintype "passive"))
      (node (ref "RT12") (pin "2") (pinfunction "2_2") (pintype "passive"))
    )
    (net (code "47") (name "Net-(Q12-G)") (class "Default")
      (node (ref "Q12") (pin "1") (pinfunction "G_1") (pintype "passive"))
      (node (ref "RQ12") (pin "1") (pinfunction "1_1") (pintype "passive"))
      (node (ref "RU12") (pin "2") (pinfunction "2_2") (pintype "passive"))
    )
    (net (code "48") (name "Net-(Q13-D)") (class "Default")
      (node (ref "Q13") (pin "3") (pinfunction "D_3") (pintype "passive"))
      (node (ref "RT13") (pin "2") (pinfunction "2_2") (pintype "passive"))
    )
    (net (code "49") (name "Net-(Q13-G)") (class "Default")
      (node (ref "Q13") (pin "1") (pinfunction "G_1") (pintype "passive"))
      (node (ref "RQ13") (pin "1") (pinfunction "1_1") (pintype "passive"))
      (node (ref "RU13") (pin "2") (pinfunction "2_2") (pintype "passive"))
    )
    (net (code "50") (name "Net-(Q14-D)") (class "Default")
      (node (ref "Q14") (pin "3") (pinfunction "D_3") (pintype "passive"))
      (node (ref "RT14") (pin "2") (pinfunction "2_2") (pintype "passive"))
    )
    (net (code "51") (name "Net-(Q14-G)") (class "Default")
      (node (ref "Q14") (pin "1") (pinfunction "G_1") (pintype "passive"))
      (node (ref "RQ14") (pin "1") (pinfunction "1_1") (pintype "passive"))
      (node (ref "RU14") (pin "2") (pinfunction "2_2") (pintype "passive"))
    )
    (net (code "52") (name "Net-(Q15-D)") (class "Default")
      (node (ref "Q15") (pin "3") (pinfunction "D_3") (pintype "passive"))
      (node (ref "RT15") (pin "2") (pinfunction "2_2") (pintype "passive"))
    )
    (net (code "53") (name "Net-(Q15-G)") (class "Default")
      (node (ref "Q15") (pin "1") (pinfunction "G_1") (pintype "passive"))
      (node (ref "RQ15") (pin "1") (pinfunction "1_1") (pintype "passive"))
      (node (ref "RU15") (pin "2") (pinfunction "2_2") (pintype "passive"))
    )
    (net (code "54") (name "Net-(Q16-D)") (class "Default")
      (node (ref "Q16") (pin "3") (pinfunction "D_3") (pintype "passive"))
      (node (ref "RT16") (pin "2") (pinfunction "2_2") (pintype "passive"))
    )
    (net (code "55") (name "Net-(Q16-G)") (class "Default")
      (node (ref "Q16") (pin "1") (pinfunction "G_1") (pintype "passive"))
      (node (ref "RQ16") (pin "1") (pinfunction "1_1") (pintype "passive"))
      (node (ref "RU16") (pin "2") (pinfunction "2_2") (pintype "passive"))
    )
    (net (code "56") (name "Net-(T1-G)") (class "Default")
      (node (ref "RB1") (pin "2") (pinfunction "2_2") (pintype "passive"))
      (node (ref "RT1") (pin "1") (pinfunction "1_1") (pintype "passive"))
      (node (ref "T1") (pin "3") (pinfunction "G_3") (pintype "bidirectional"))
    )
    (net (code "57") (name "Net-(T1-M2)") (class "Default")
      (node (ref "S01") (pin "1") (pinfunction "1_1") (pintype "passive"))
      (node (ref "SP1") (pin "2") (pinfunction "2_2") (pintype "passive"))
      (node (ref "T1") (pin "2") (pinfunction "M2_2") (pintype "bidirectional"))
      (node (ref "T1") (pin "4") (pinfunction "M2-4_4") (pintype "bidirectional"))
      (node (ref "TVS1") (pin "A") (pinfunction "A_A") (pintype "passive"))
    )
    (net (code "58") (name "Net-(T2-G)") (class "Default")
      (node (ref "RB2") (pin "2") (pinfunction "2_2") (pintype "passive"))
      (node (ref "RT2") (pin "1") (pinfunction "1_1") (pintype "passive"))
      (node (ref "T2") (pin "3") (pinfunction "G_3") (pintype "bidirectional"))
    )
    (net (code "59") (name "Net-(T2-M2)") (class "Default")
      (node (ref "S01") (pin "2") (pinfunction "2_2") (pintype "passive"))
      (node (ref "SP2") (pin "2") (pinfunction "2_2") (pintype "passive"))
      (node (ref "T2") (pin "2") (pinfunction "M2_2") (pintype "bidirectional"))
      (node (ref "T2") (pin "4") (pinfunction "M2-4_4") (pintype "bidirectional"))
      (node (ref "TVS2") (pin "A") (pinfunction "A_A") (pintype "passive"))
    )
    (net (code "60") (name "Net-(T3-G)") (class "Default")
      (node (ref "RB3") (pin "2") (pinfunction "2_2") (pintype "passive"))
      (node (ref "RT3") (pin "1") (pinfunction "1_1") (pintype "passive"))
      (node (ref "T3") (pin "3") (pinfunction "G_3") (pintype "bidirectional"))
    )
    (net (code "61") (name "Net-(T3-M2)") (class "Default")
      (node (ref "S01") (pin "3") (pinfunction "3_3") (pintype "passive"))
      (node (ref "SP3") (pin "2") (pinfunction "2_2") (pintype "passive"))
      (node (ref "T3") (pin "2") (pinfunction "M2_2") (pintype "bidirectional"))
      (node (ref "T3") (pin "4") (pinfunction "M2-4_4") (pintype "bidirectional"))
      (node (ref "TVS3") (pin "A") (pinfunction "A_A") (pintype "passive"))
    )
    (net (code "62") (name "Net-(T4-G)") (class "Default")
      (node (ref "RB4") (pin "2") (pinfunction "2_2") (pintype "passive"))
      (node (ref "RT4") (pin "1") (pinfunction "1_1") (pintype "passive"))
      (node (ref "T4") (pin "3") (pinfunction "G_3") (pintype "bidirectional"))
    )
    (net (code "63") (name "Net-(T4-M2)") (class "Default")
      (node (ref "S01") (pin "4") (pinfunction "4_4") (pintype "passive"))
      (node (ref "SP4") (pin "2") (pinfunction "2_2") (pintype "passive"))
      (node (ref "T4") (pin "2") (pinfunction "M2_2") (pintype "bidirectional"))
      (node (ref "T4") (pin "4") (pinfunction "M2-4_4") (pintype "bidirectional"))
      (node (ref "TVS4") (pin "A") (pinfunction "A_A") (pintype "passive"))
    )
    (net (code "64") (name "Net-(T5-G)") (class "Default")
      (node (ref "RB5") (pin "2") (pinfunction "2_2") (pintype "passive"))
      (node (ref "RT5") (pin "1") (pinfunction "1_1") (pintype "passive"))
      (node (ref "T5") (pin "3") (pinfunction "G_3") (pintype "bidirectional"))
    )
    (net (code "65") (name "Net-(T5-M2)") (class "Default")
      (node (ref "S01") (pin "5") (pinfunction "5_5") (pintype "passive"))
      (node (ref "SP5") (pin "2") (pinfunction "2_2") (pintype "passive"))
      (node (ref "T5") (pin "2") (pinfunction "M2_2") (pintype "bidirectional"))
      (node (ref "T5") (pin "4") (pinfunction "M2-4_4") (pintype "bidirectional"))
      (node (ref "TVS5") (pin "A") (pinfunction "A_A") (pintype "passive"))
    )
    (net (code "66") (name "Net-(T6-G)") (class "Default")
      (node (ref "RB6") (pin "2") (pinfunction "2_2") (pintype "passive"))
      (node (ref "RT6") (pin "1") (pinfunction "1_1") (pintype "passive"))
      (node (ref "T6") (pin "3") (pinfunction "G_3") (pintype "bidirectional"))
    )
    (net (code "67") (name "Net-(T6-M2)") (class "Default")
      (node (ref "S01") (pin "6") (pinfunction "6_6") (pintype "passive"))
      (node (ref "SP6") (pin "2") (pinfunction "2_2") (pintype "passive"))
      (node (ref "T6") (pin "2") (pinfunction "M2_2") (pintype "bidirectional"))
      (node (ref "T6") (pin "4") (pinfunction "M2-4_4") (pintype "bidirectional"))
      (node (ref "TVS6") (pin "A") (pinfunction "A_A") (pintype "passive"))
    )
    (net (code "68") (name "Net-(T7-G)") (class "Default")
      (node (ref "RB7") (pin "2") (pinfunction "2_2") (pintype "passive"))
      (node (ref "RT7") (pin "1") (pinfunction "1_1") (pintype "passive"))
      (node (ref "T7") (pin "3") (pinfunction "G_3") (pintype "bidirectional"))
    )
    (net (code "69") (name "Net-(T7-M2)") (class "Default")
      (node (ref "S01") (pin "7") (pinfunction "7_7") (pintype "passive"))
      (node (ref "SP7") (pin "2") (pinfunction "2_2") (pintype "passive"))
      (node (ref "T7") (pin "2") (pinfunction "M2_2") (pintype "bidirectional"))
      (node (ref "T7") (pin "4") (pinfunction "M2-4_4") (pintype "bidirectional"))
      (node (ref "TVS7") (pin "A") (pinfunction "A_A") (pintype "passive"))
    )
    (net (code "70") (name "Net-(T8-G)") (class "Default")
      (node (ref "RB8") (pin "2") (pinfunction "2_2") (pintype "passive"))
      (node (ref "RT8") (pin "1") (pinfunction "1_1") (pintype "passive"))
      (node (ref "T8") (pin "3") (pinfunction "G_3") (pintype "bidirectional"))
    )
    (net (code "71") (name "Net-(T8-M2)") (class "Default")
      (node (ref "S01") (pin "8") (pinfunction "8_8") (pintype "passive"))
      (node (ref "SP8") (pin "2") (pinfunction "2_2") (pintype "passive"))
      (node (ref "T8") (pin "2") (pinfunction "M2_2") (pintype "bidirectional"))
      (node (ref "T8") (pin "4") (pinfunction "M2-4_4") (pintype "bidirectional"))
      (node (ref "TVS8") (pin "A") (pinfunction "A_A") (pintype "passive"))
    )
    (net (code "72") (name "Net-(T9-G)") (class "Default")
      (node (ref "RB9") (pin "2") (pinfunction "2_2") (pintype "passive"))
      (node (ref "RT9") (pin "1") (pinfunction "1_1") (pintype "passive"))
      (node (ref "T9") (pin "3") (pinfunction "G_3") (pintype "bidirectional"))
    )
    (net (code "73") (name "Net-(T9-M2)") (class "Default")
      (node (ref "S02") (pin "1") (pinfunction "1_1") (pintype "passive"))
      (node (ref "SP9") (pin "2") (pinfunction "2_2") (pintype "passive"))
      (node (ref "T9") (pin "2") (pinfunction "M2_2") (pintype "bidirectional"))
      (node (ref "T9") (pin "4") (pinfunction "M2-4_4") (pintype "bidirectional"))
      (node (ref "TVS9") (pin "A") (pinfunction "A_A") (pintype "passive"))
    )
    (net (code "74") (name "Net-(T10-G)") (class "Default")
      (node (ref "RB10") (pin "2") (pinfunction "2_2") (pintype "passive"))
      (node (ref "RT10") (pin "1") (pinfunction "1_1") (pintype "passive"))
      (node (ref "T10") (pin "3") (pinfunction "G_3") (pintype "bidirectional"))
    )
    (net (code "75") (name "Net-(T10-M2)") (class "Default")
      (node (ref "S02") (pin "2") (pinfunction "2_2") (pintype "passive"))
      (node (ref "SP10") (pin "2") (pinfunction "2_2") (pintype "passive"))
      (node (ref "T10") (pin "2") (pinfunction "M2_2") (pintype "bidirectional"))
      (node (ref "T10") (pin "4") (pinfunction "M2-4_4") (pintype "bidirectional"))
      (node (ref "TVS10") (pin "A") (pinfunction "A_A") (pintype "passive"))
    )
    (net (code "76") (name "Net-(T11-G)") (class "Default")
      (node (ref "RB11") (pin "2") (pinfunction "2_2") (pintype "passive"))
      (node (ref "RT11") (pin "1") (pinfunction "1_1") (pintype "passive"))
      (node (ref "T11") (pin "3") (pinfunction "G_3") (pintype "bidirectional"))
    )
    (net (code "77") (name "Net-(T11-M2)") (class "Default")
      (node (ref "S02") (pin "3") (pinfunction "3_3") (pintype "passive"))
      (node (ref "SP11") (pin "2") (pinfunction "2_2") (pintype "passive"))
      (node (ref "T11") (pin "2") (pinfunction "M2_2") (pintype "bidirectional"))
      (node (ref "T11") (pin "4") (pinfunction "M2-4_4") (pintype "bidirectional"))
      (node (ref "TVS11") (pin "A") (pinfunction "A_A") (pintype "passive"))
    )
    (net (code "78") (name "Net-(T12-G)") (class "Default")
      (node (ref "RB12") (pin "2") (pinfunction "2_2") (pintype "passive"))
      (node (ref "RT12") (pin "1") (pinfunction "1_1") (pintype "passive"))
      (node (ref "T12") (pin "3") (pinfunction "G_3") (pintype "bidirectional"))
    )
    (net (code "79") (name "Net-(T12-M2)") (class "Default")
      (node (ref "S02") (pin "4") (pinfunction "4_4") (pintype "passive"))
      (node (ref "SP12") (pin "2") (pinfunction "2_2") (pintype "passive"))
      (node (ref "T12") (pin "2") (pinfunction "M2_2") (pintype "bidirectional"))
      (node (ref "T12") (pin "4") (pinfunction "M2-4_4") (pintype "bidirectional"))
      (node (ref "TVS12") (pin "A") (pinfunction "A_A") (pintype "passive"))
    )
    (net (code "80") (name "Net-(T13-G)") (class "Default")
      (node (ref "RB13") (pin "2") (pinfunction "2_2") (pintype "passive"))
      (node (ref "RT13") (pin "1") (pinfunction "1_1") (pintype "passive"))
      (node (ref "T13") (pin "3") (pinfunction "G_3") (pintype "bidirectional"))
    )
    (net (code "81") (name "Net-(T13-M2)") (class "Default")
      (node (ref "S02") (pin "5") (pinfunction "5_5") (pintype "passive"))
      (node (ref "SP13") (pin "2") (pinfunction "2_2") (pintype "passive"))
      (node (ref "T13") (pin "2") (pinfunction "M2_2") (pintype "bidirectional"))
      (node (ref "T13") (pin "4") (pinfunction "M2-4_4") (pintype "bidirectional"))
      (node (ref "TVS13") (pin "A") (pinfunction "A_A") (pintype "passive"))
    )
    (net (code "82") (name "Net-(T14-G)") (class "Default")
      (node (ref "RB14") (pin "2") (pinfunction "2_2") (pintype "passive"))
      (node (ref "RT14") (pin "1") (pinfunction "1_1") (pintype "passive"))
      (node (ref "T14") (pin "3") (pinfunction "G_3") (pintype "bidirectional"))
    )
    (net (code "83") (name "Net-(T14-M2)") (class "Default")
      (node (ref "S02") (pin "6") (pinfunction "6_6") (pintype "passive"))
      (node (ref "SP14") (pin "2") (pinfunction "2_2") (pintype "passive"))
      (node (ref "T14") (pin "2") (pinfunction "M2_2") (pintype "bidirectional"))
      (node (ref "T14") (pin "4") (pinfunction "M2-4_4") (pintype "bidirectional"))
      (node (ref "TVS14") (pin "A") (pinfunction "A_A") (pintype "passive"))
    )
    (net (code "84") (name "Net-(T15-G)") (class "Default")
      (node (ref "RB15") (pin "2") (pinfunction "2_2") (pintype "passive"))
      (node (ref "RT15") (pin "1") (pinfunction "1_1") (pintype "passive"))
      (node (ref "T15") (pin "3") (pinfunction "G_3") (pintype "bidirectional"))
    )
    (net (code "85") (name "Net-(T15-M2)") (class "Default")
      (node (ref "S02") (pin "7") (pinfunction "7_7") (pintype "passive"))
      (node (ref "SP15") (pin "2") (pinfunction "2_2") (pintype "passive"))
      (node (ref "T15") (pin "2") (pinfunction "M2_2") (pintype "bidirectional"))
      (node (ref "T15") (pin "4") (pinfunction "M2-4_4") (pintype "bidirectional"))
      (node (ref "TVS15") (pin "A") (pinfunction "A_A") (pintype "passive"))
    )
    (net (code "86") (name "Net-(T16-G)") (class "Default")
      (node (ref "RB16") (pin "2") (pinfunction "2_2") (pintype "passive"))
      (node (ref "RT16") (pin "1") (pinfunction "1_1") (pintype "passive"))
      (node (ref "T16") (pin "3") (pinfunction "G_3") (pintype "bidirectional"))
    )
    (net (code "87") (name "Net-(T16-M2)") (class "Default")
      (node (ref "S02") (pin "8") (pinfunction "8_8") (pintype "passive"))
      (node (ref "SP16") (pin "2") (pinfunction "2_2") (pintype "passive"))
      (node (ref "T16") (pin "2") (pinfunction "M2_2") (pintype "bidirectional"))
      (node (ref "T16") (pin "4") (pinfunction "M2-4_4") (pintype "bidirectional"))
      (node (ref "TVS16") (pin "A") (pinfunction "A_A") (pintype "passive"))
    )
    (net (code "88") (name "unconnected-(JEXT1-Pad1)") (class "Default")
      (node (ref "JEXT1") (pin "1") (pinfunction "1_1") (pintype "passive"))
    )
    (net (code "89") (name "unconnected-(JEXT1-Pad2)") (class "Default")
      (node (ref "JEXT1") (pin "2") (pinfunction "2_2") (pintype "passive"))
    )
    (net (code "90") (name "unconnected-(JEXT1-Pad3)") (class "Default")
      (node (ref "JEXT1") (pin "3") (pinfunction "3_3") (pintype "passive"))
    )
    (net (code "91") (name "unconnected-(JEXT1-Pad4)") (class "Default")
      (node (ref "JEXT1") (pin "4") (pinfunction "4_4") (pintype "passive"))
    )
    (net (code "92") (name "unconnected-(JEXT2-Pad1)") (class "Default")
      (node (ref "JEXT2") (pin "1") (pinfunction "1_1") (pintype "passive"))
    )
    (net (code "93") (name "unconnected-(JEXT2-Pad2)") (class "Default")
      (node (ref "JEXT2") (pin "2") (pinfunction "2_2") (pintype "passive"))
    )
    (net (code "94") (name "unconnected-(JEXT2-Pad3)") (class "Default")
      (node (ref "JEXT2") (pin "3") (pinfunction "3_3") (pintype "passive"))
    )
    (net (code "95") (name "unconnected-(JEXT2-Pad4)") (class "Default")
      (node (ref "JEXT2") (pin "4") (pinfunction "4_4") (pintype "passive"))
    )
    (net (code "96") (name "unconnected-(PCF8575-~{INT}-Pad1)") (class "Default")
      (node (ref "PCF8575") (pin "1") (pinfunction "~{INT}_1") (pintype "bidirectional"))
    )
  )
)
